# RCDongle.net
KiCad netlist of a schematic drawn in EAGLE
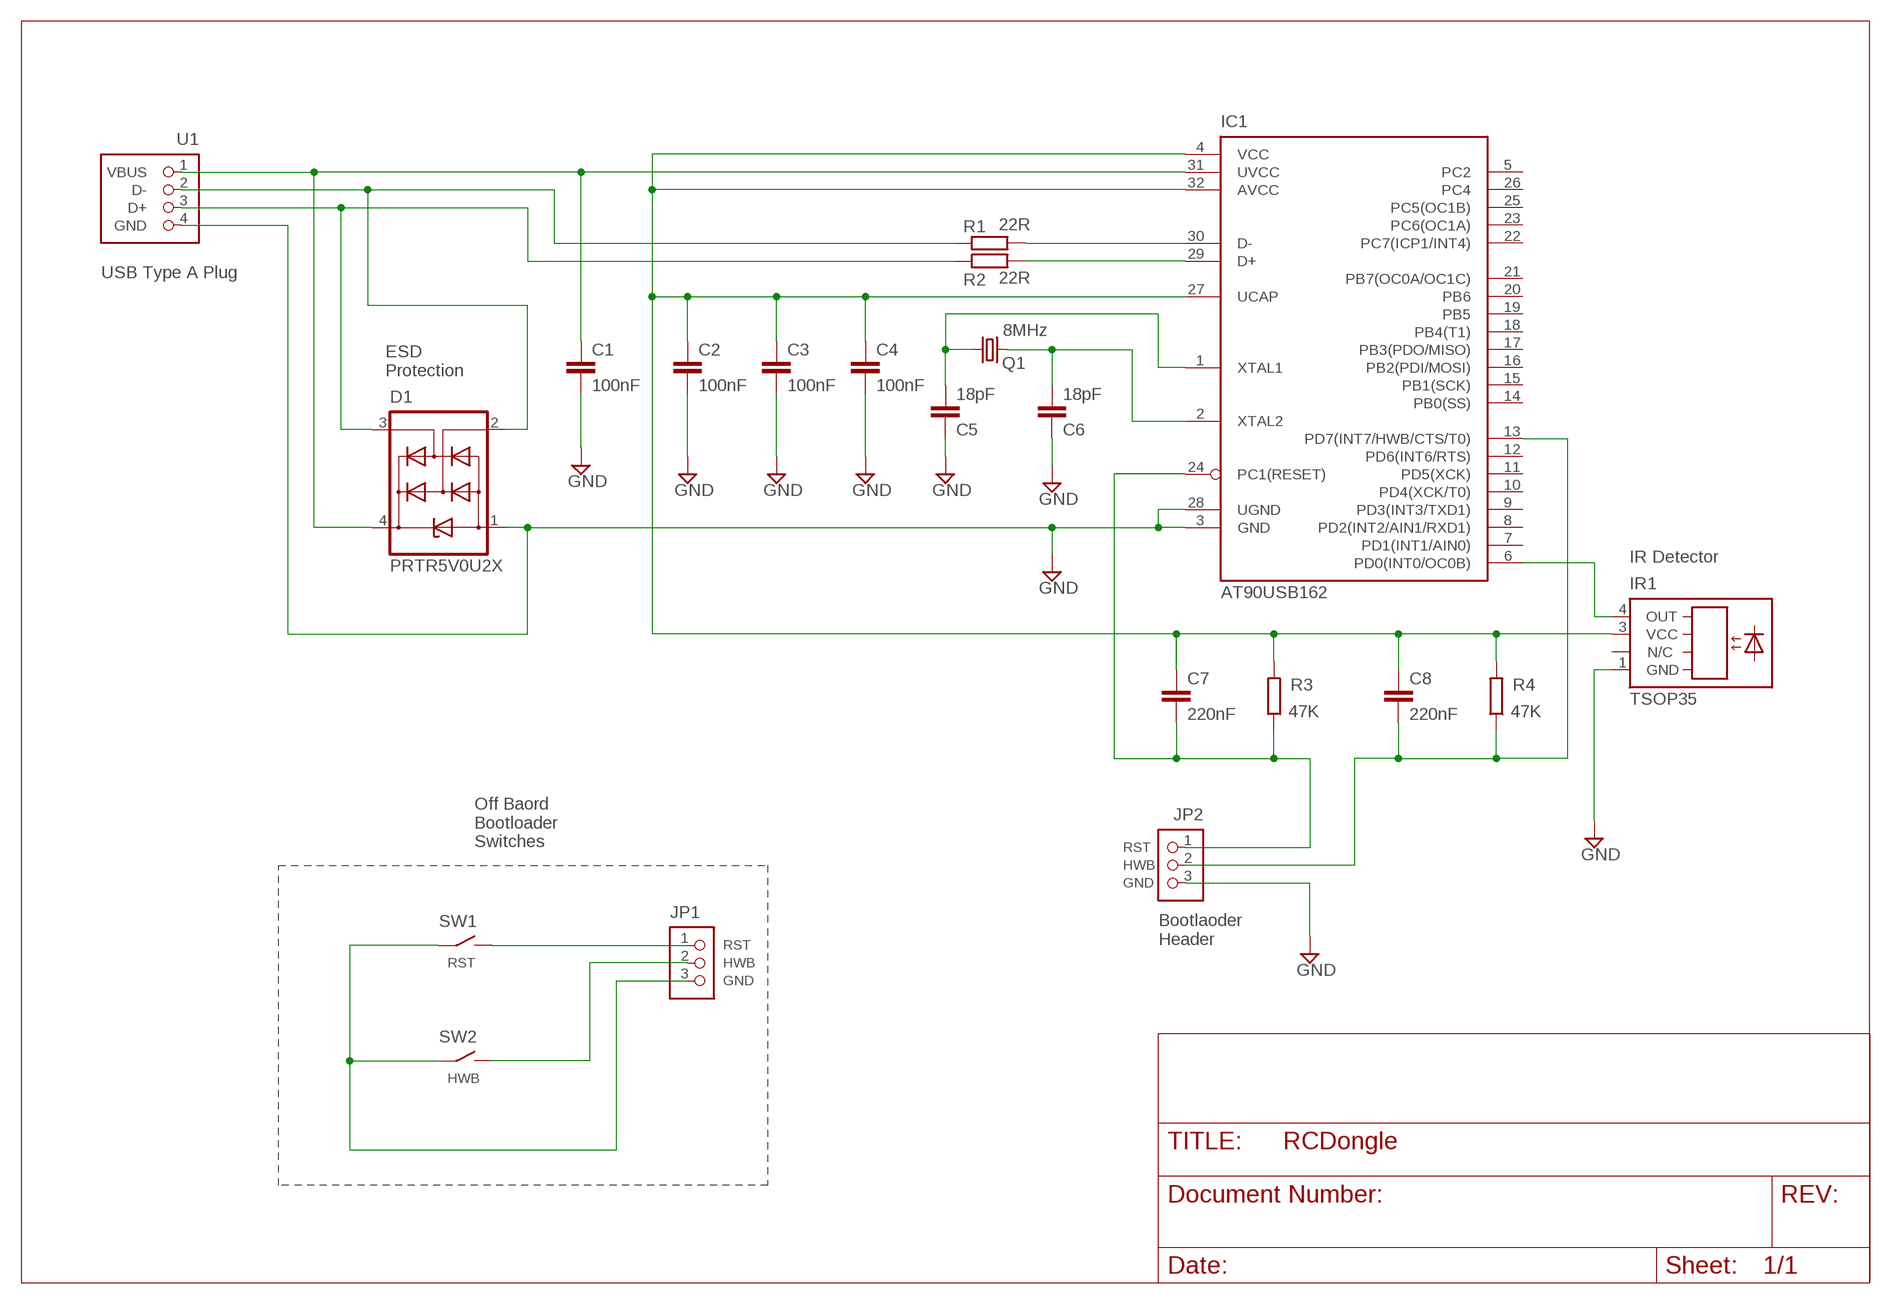
[diagram p0: schematic, sheet 1]

(export (version "E")
  (design (tool "Eeschema 10.0.6"))
  (components
    (comp (ref "C1")
      (value "100nF")
      (footprint "eagle-import:C0805")
      (libsource (lib "eagle-import") (part "C-EUC0805"))
    )
    (comp (ref "C2")
      (value "100nF")
      (footprint "eagle-import:C0805")
      (libsource (lib "eagle-import") (part "C-EUC0805"))
    )
    (comp (ref "C3")
      (value "100nF")
      (footprint "eagle-import:C0805")
      (libsource (lib "eagle-import") (part "C-EUC0805"))
    )
    (comp (ref "C4")
      (value "100nF")
      (footprint "eagle-import:C0805")
      (libsource (lib "eagle-import") (part "C-EUC0805"))
    )
    (comp (ref "C5")
      (value "18pF")
      (footprint "eagle-import:C0805")
      (libsource (lib "eagle-import") (part "C-EUC0805"))
    )
    (comp (ref "C6")
      (value "18pF")
      (footprint "eagle-import:C0805")
      (libsource (lib "eagle-import") (part "C-EUC0805"))
    )
    (comp (ref "C7")
      (value "220nF")
      (footprint "eagle-import:C0805")
      (libsource (lib "eagle-import") (part "C-EUC0805"))
    )
    (comp (ref "C8")
      (value "220nF")
      (footprint "eagle-import:C0805")
      (libsource (lib "eagle-import") (part "C-EUC0805"))
    )
    (comp (ref "D1")
      (value "PRTR5V0U2X")
      (footprint "eagle-import:P-SOT143BE")
      (libsource (lib "eagle-import") (part "PRTR5V0U2X"))
    )
    (comp (ref "IC1")
      (value "AT90USB162")
      (footprint "eagle-import:P-TQFP32")
      (libsource (lib "eagle-import") (part "AT90USB162"))
    )
    (comp (ref "IR1")
      (value "TSOP35")
      (footprint "eagle-import:P-TSOP35")
      (libsource (lib "eagle-import") (part "TSOP35"))
    )
    (comp (ref "JP1")
      (value "HEADER-1X03")
      (footprint "eagle-import:P-1X03")
      (libsource (lib "eagle-import") (part "HEADER-1X03"))
    )
    (comp (ref "JP2")
      (value "HEADER-1X03")
      (footprint "eagle-import:P-1X03")
      (libsource (lib "eagle-import") (part "HEADER-1X03"))
    )
    (comp (ref "Q1")
      (value "8MHz")
      (footprint "eagle-import:CSM-7X-DU")
      (libsource (lib "eagle-import") (part "CSM-7X-DU"))
    )
    (comp (ref "R1")
      (value "22R")
      (footprint "eagle-import:M0805")
      (libsource (lib "eagle-import") (part "R-EU_M0805"))
    )
    (comp (ref "R2")
      (value "22R")
      (footprint "eagle-import:M0805")
      (libsource (lib "eagle-import") (part "R-EU_M0805"))
    )
    (comp (ref "R3")
      (value "47K")
      (footprint "eagle-import:M0805")
      (libsource (lib "eagle-import") (part "R-EU_M0805"))
    )
    (comp (ref "R4")
      (value "47K")
      (footprint "eagle-import:M0805")
      (libsource (lib "eagle-import") (part "R-EU_M0805"))
    )
    (comp (ref "SW1")
      (value "SWITCH-2PIN")
      (footprint "eagle-import:P-SWITCH-SMT-DTSM31NV")
      (libsource (lib "eagle-import") (part "SWITCH-2PIN"))
    )
    (comp (ref "SW2")
      (value "SWITCH-2PIN")
      (footprint "eagle-import:P-SWITCH-SMT-DTSM31NV")
      (libsource (lib "eagle-import") (part "SWITCH-2PIN"))
    )
    (comp (ref "U1")
      (value "USB-TYPEA-PLUG")
      (footprint "eagle-import:P-USB-TYPEA-PLUG")
      (libsource (lib "eagle-import") (part "USB-TYPEA-PLUG"))
    )
  )
  (nets
    (net (code "1") (name "GND") (class "Default")
      (node (ref "C1") (pin "2") (pinfunction "2_2") (pintype "passive"))
      (node (ref "C2") (pin "2") (pinfunction "2_2") (pintype "passive"))
      (node (ref "C3") (pin "2") (pinfunction "2_2") (pintype "passive"))
      (node (ref "C4") (pin "2") (pinfunction "2_2") (pintype "passive"))
      (node (ref "C5") (pin "1") (pinfunction "1_1") (pintype "passive"))
      (node (ref "C6") (pin "1") (pinfunction "1_1") (pintype "passive"))
      (node (ref "D1") (pin "1") (pinfunction "P$1_1") (pintype "bidirectional"))
      (node (ref "IC1") (pin "28") (pinfunction "UGND_28") (pintype "power_in"))
      (node (ref "IC1") (pin "3") (pinfunction "GND_3") (pintype "power_in"))
      (node (ref "IR1") (pin "1") (pinfunction "GND_1") (pintype "bidirectional"))
      (node (ref "JP2") (pin "3") (pinfunction "3_3") (pintype "bidirectional"))
      (node (ref "U1") (pin "4") (pinfunction "GND_4") (pintype "bidirectional"))
    )
    (net (code "2") (name "Net-(D1-P$2)") (class "Default")
      (node (ref "D1") (pin "2") (pinfunction "P$2_2") (pintype "bidirectional"))
      (node (ref "R1") (pin "1") (pinfunction "1_1") (pintype "passive"))
      (node (ref "U1") (pin "2") (pinfunction "D-_2") (pintype "bidirectional"))
    )
    (net (code "3") (name "Net-(D1-P$3)") (class "Default")
      (node (ref "D1") (pin "3") (pinfunction "P$3_3") (pintype "bidirectional"))
      (node (ref "R2") (pin "1") (pinfunction "1_1") (pintype "passive"))
      (node (ref "U1") (pin "3") (pinfunction "D+_3") (pintype "bidirectional"))
    )
    (net (code "4") (name "Net-(D1-P$4)") (class "Default")
      (node (ref "C1") (pin "1") (pinfunction "1_1") (pintype "passive"))
      (node (ref "D1") (pin "4") (pinfunction "P$4_4") (pintype "bidirectional"))
      (node (ref "IC1") (pin "31") (pinfunction "UVCC_31") (pintype "power_in"))
      (node (ref "U1") (pin "1") (pinfunction "VBUS_1") (pintype "bidirectional"))
    )
    (net (code "5") (name "Net-(IC1-AVCC)") (class "Default")
      (node (ref "C2") (pin "1") (pinfunction "1_1") (pintype "passive"))
      (node (ref "C3") (pin "1") (pinfunction "1_1") (pintype "passive"))
      (node (ref "C4") (pin "1") (pinfunction "1_1") (pintype "passive"))
      (node (ref "C7") (pin "1") (pinfunction "1_1") (pintype "passive"))
      (node (ref "C8") (pin "1") (pinfunction "1_1") (pintype "passive"))
      (node (ref "IC1") (pin "27") (pinfunction "UCAP_27") (pintype "bidirectional"))
      (node (ref "IC1") (pin "32") (pinfunction "AVCC_32") (pintype "power_in"))
      (node (ref "IC1") (pin "4") (pinfunction "VCC_4") (pintype "power_in"))
      (node (ref "IR1") (pin "3") (pinfunction "VCC_3") (pintype "bidirectional"))
      (node (ref "R3") (pin "2") (pinfunction "2_2") (pintype "passive"))
      (node (ref "R4") (pin "2") (pinfunction "2_2") (pintype "passive"))
    )
    (net (code "6") (name "Net-(IC1-D+)") (class "Default")
      (node (ref "IC1") (pin "29") (pinfunction "D+_29") (pintype "bidirectional"))
      (node (ref "R2") (pin "2") (pinfunction "2_2") (pintype "passive"))
    )
    (net (code "7") (name "Net-(IC1-D-)") (class "Default")
      (node (ref "IC1") (pin "30") (pinfunction "D-_30") (pintype "bidirectional"))
      (node (ref "R1") (pin "2") (pinfunction "2_2") (pintype "passive"))
    )
    (net (code "8") (name "Net-(IC1-PC1(RESET))") (class "Default")
      (node (ref "C7") (pin "2") (pinfunction "2_2") (pintype "passive"))
      (node (ref "IC1") (pin "24") (pinfunction "PC1(RESET)_24") (pintype "bidirectional"))
      (node (ref "JP2") (pin "1") (pinfunction "1_1") (pintype "bidirectional"))
      (node (ref "R3") (pin "1") (pinfunction "1_1") (pintype "passive"))
    )
    (net (code "9") (name "Net-(IC1-PD0(INT0{slash}OC0B))") (class "Default")
      (node (ref "IC1") (pin "6") (pinfunction "PD0(INT0/OC0B)_6") (pintype "bidirectional"))
      (node (ref "IR1") (pin "4") (pinfunction "OUT_4") (pintype "bidirectional"))
    )
    (net (code "10") (name "Net-(IC1-PD7(INT7{slash}HWB{slash}CTS{slash}T0))") (class "Default")
      (node (ref "C8") (pin "2") (pinfunction "2_2") (pintype "passive"))
      (node (ref "IC1") (pin "13") (pinfunction "PD7(INT7/HWB/CTS/T0)_13") (pintype "bidirectional"))
      (node (ref "JP2") (pin "2") (pinfunction "2_2") (pintype "bidirectional"))
      (node (ref "R4") (pin "1") (pinfunction "1_1") (pintype "passive"))
    )
    (net (code "11") (name "Net-(IC1-XTAL1)") (class "Default")
      (node (ref "C5") (pin "2") (pinfunction "2_2") (pintype "passive"))
      (node (ref "IC1") (pin "1") (pinfunction "XTAL1_1") (pintype "bidirectional"))
      (node (ref "Q1") (pin "2") (pinfunction "2_2") (pintype "passive"))
    )
    (net (code "12") (name "Net-(IC1-XTAL2)") (class "Default")
      (node (ref "C6") (pin "2") (pinfunction "2_2") (pintype "passive"))
      (node (ref "IC1") (pin "2") (pinfunction "XTAL2_2") (pintype "bidirectional"))
      (node (ref "Q1") (pin "1") (pinfunction "1_1") (pintype "passive"))
    )
    (net (code "13") (name "Net-(SW1-P$1)") (class "Default")
      (node (ref "JP1") (pin "3") (pinfunction "3_3") (pintype "bidirectional"))
      (node (ref "SW1") (pin "1") (pinfunction "P$1_1") (pintype "bidirectional"))
      (node (ref "SW2") (pin "1") (pinfunction "P$1_1") (pintype "bidirectional"))
    )
    (net (code "14") (name "Net-(SW1-P$2)") (class "Default")
      (node (ref "JP1") (pin "1") (pinfunction "1_1") (pintype "bidirectional"))
      (node (ref "SW1") (pin "2") (pinfunction "P$2_2") (pintype "bidirectional"))
    )
    (net (code "15") (name "Net-(SW2-P$2)") (class "Default")
      (node (ref "JP1") (pin "2") (pinfunction "2_2") (pintype "bidirectional"))
      (node (ref "SW2") (pin "2") (pinfunction "P$2_2") (pintype "bidirectional"))
    )
    (net (code "16") (name "unconnected-(IC1-PB0(SS)-Pad14)") (class "Default")
      (node (ref "IC1") (pin "14") (pinfunction "PB0(SS)_14") (pintype "bidirectional"))
    )
    (net (code "17") (name "unconnected-(IC1-PB1(SCK)-Pad15)") (class "Default")
      (node (ref "IC1") (pin "15") (pinfunction "PB1(SCK)_15") (pintype "bidirectional"))
    )
    (net (code "18") (name "unconnected-(IC1-PB2(PDI{slash}MOSI)-Pad16)") (class "Default")
      (node (ref "IC1") (pin "16") (pinfunction "PB2(PDI/MOSI)_16") (pintype "bidirectional"))
    )
    (net (code "19") (name "unconnected-(IC1-PB3(PDO{slash}MISO)-Pad17)") (class "Default")
      (node (ref "IC1") (pin "17") (pinfunction "PB3(PDO/MISO)_17") (pintype "bidirectional"))
    )
    (net (code "20") (name "unconnected-(IC1-PB4(T1)-Pad18)") (class "Default")
      (node (ref "IC1") (pin "18") (pinfunction "PB4(T1)_18") (pintype "bidirectional"))
    )
    (net (code "21") (name "unconnected-(IC1-PB5-Pad19)") (class "Default")
      (node (ref "IC1") (pin "19") (pinfunction "PB5_19") (pintype "bidirectional"))
    )
    (net (code "22") (name "unconnected-(IC1-PB6-Pad20)") (class "Default")
      (node (ref "IC1") (pin "20") (pinfunction "PB6_20") (pintype "bidirectional"))
    )
    (net (code "23") (name "unconnected-(IC1-PB7(OC0A{slash}OC1C)-Pad21)") (class "Default")
      (node (ref "IC1") (pin "21") (pinfunction "PB7(OC0A/OC1C)_21") (pintype "bidirectional"))
    )
    (net (code "24") (name "unconnected-(IC1-PC2-Pad5)") (class "Default")
      (node (ref "IC1") (pin "5") (pinfunction "PC2_5") (pintype "bidirectional"))
    )
    (net (code "25") (name "unconnected-(IC1-PC4-Pad26)") (class "Default")
      (node (ref "IC1") (pin "26") (pinfunction "PC4_26") (pintype "bidirectional"))
    )
    (net (code "26") (name "unconnected-(IC1-PC5(OC1B)-Pad25)") (class "Default")
      (node (ref "IC1") (pin "25") (pinfunction "PC5(OC1B)_25") (pintype "bidirectional"))
    )
    (net (code "27") (name "unconnected-(IC1-PC6(OC1A)-Pad23)") (class "Default")
      (node (ref "IC1") (pin "23") (pinfunction "PC6(OC1A)_23") (pintype "bidirectional"))
    )
    (net (code "28") (name "unconnected-(IC1-PC7(ICP1{slash}INT4)-Pad22)") (class "Default")
      (node (ref "IC1") (pin "22") (pinfunction "PC7(ICP1/INT4)_22") (pintype "bidirectional"))
    )
    (net (code "29") (name "unconnected-(IC1-PD1(INT1{slash}AIN0)-Pad7)") (class "Default")
      (node (ref "IC1") (pin "7") (pinfunction "PD1(INT1/AIN0)_7") (pintype "bidirectional"))
    )
    (net (code "30") (name "unconnected-(IC1-PD2(INT2{slash}AIN1{slash}RXD1)-Pad8)") (class "Default")
      (node (ref "IC1") (pin "8") (pinfunction "PD2(INT2/AIN1/RXD1)_8") (pintype "bidirectional"))
    )
    (net (code "31") (name "unconnected-(IC1-PD3(INT3{slash}TXD1)-Pad9)") (class "Default")
      (node (ref "IC1") (pin "9") (pinfunction "PD3(INT3/TXD1)_9") (pintype "bidirectional"))
    )
    (net (code "32") (name "unconnected-(IC1-PD4(XCK{slash}T0)-Pad10)") (class "Default")
      (node (ref "IC1") (pin "10") (pinfunction "PD4(XCK/T0)_10") (pintype "bidirectional"))
    )
    (net (code "33") (name "unconnected-(IC1-PD5(XCK)-Pad11)") (class "Default")
      (node (ref "IC1") (pin "11") (pinfunction "PD5(XCK)_11") (pintype "bidirectional"))
    )
    (net (code "34") (name "unconnected-(IC1-PD6(INT6{slash}RTS)-Pad12)") (class "Default")
      (node (ref "IC1") (pin "12") (pinfunction "PD6(INT6/RTS)_12") (pintype "bidirectional"))
    )
  )
)
